# power.net
KiCad netlist of a schematic drawn in EAGLE
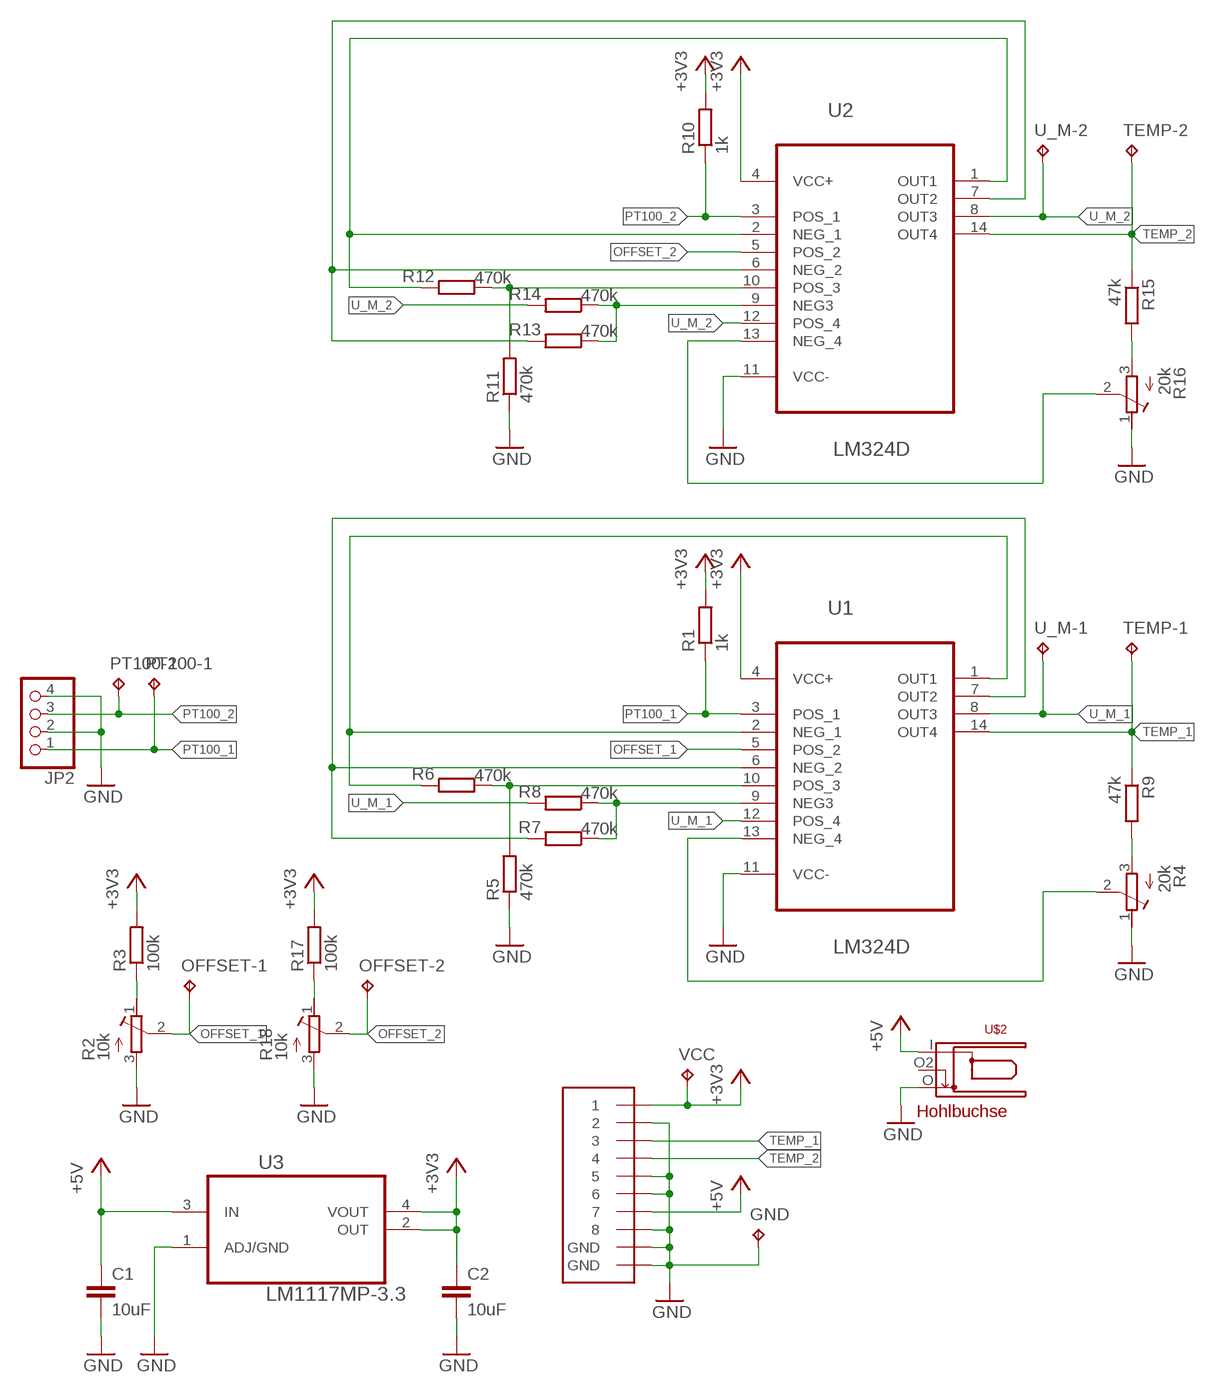
[diagram p0: schematic, sheet 1]

(export (version "E")
  (design (tool "Eeschema 10.0.6"))
  (components
    (comp (ref "C1")
      (value "10uF")
      (footprint "eagle-import:C0805")
      (libsource (lib "eagle-import") (part "C-EUC0805"))
    )
    (comp (ref "C2")
      (value "10uF")
      (footprint "eagle-import:C0805")
      (libsource (lib "eagle-import") (part "C-EUC0805"))
    )
    (comp (ref "GND")
      (value "TPB1,27")
      (footprint "eagle-import:B1,27")
      (libsource (lib "eagle-import") (part "TPB1,27"))
    )
    (comp (ref "JP2")
      (value "PINHD-1X4/90")
      (footprint "eagle-import:1X04_90")
      (libsource (lib "eagle-import") (part "PINHD-1X4/90"))
    )
    (comp (ref "OFFSET-1")
      (value "TPB1,27")
      (footprint "eagle-import:B1,27")
      (libsource (lib "eagle-import") (part "TPB1,27"))
    )
    (comp (ref "OFFSET-2")
      (value "TPB1,27")
      (footprint "eagle-import:B1,27")
      (libsource (lib "eagle-import") (part "TPB1,27"))
    )
    (comp (ref "PT100-1")
      (value "TPB1,27")
      (footprint "eagle-import:B1,27")
      (libsource (lib "eagle-import") (part "TPB1,27"))
    )
    (comp (ref "PT100-2")
      (value "TPB1,27")
      (footprint "eagle-import:B1,27")
      (libsource (lib "eagle-import") (part "TPB1,27"))
    )
    (comp (ref "R1")
      (value "1k")
      (footprint "eagle-import:R0805")
      (libsource (lib "eagle-import") (part "R-EU_R0805"))
    )
    (comp (ref "R2")
      (value "10k")
      (footprint "eagle-import:RTRIMT93YB")
      (libsource (lib "eagle-import") (part "R-TRIMMT93YB"))
    )
    (comp (ref "R3")
      (value "100k")
      (footprint "eagle-import:R0805")
      (libsource (lib "eagle-import") (part "R-EU_R0805"))
    )
    (comp (ref "R4")
      (value "20k")
      (footprint "eagle-import:RTRIMT93YB")
      (libsource (lib "eagle-import") (part "R-TRIMMT93YB"))
    )
    (comp (ref "R5")
      (value "470k")
      (footprint "eagle-import:R0805")
      (libsource (lib "eagle-import") (part "R-EU_R0805"))
    )
    (comp (ref "R6")
      (value "470k")
      (footprint "eagle-import:R0805")
      (libsource (lib "eagle-import") (part "R-EU_R0805"))
    )
    (comp (ref "R7")
      (value "470k")
      (footprint "eagle-import:R0805")
      (libsource (lib "eagle-import") (part "R-EU_R0805"))
    )
    (comp (ref "R8")
      (value "470k")
      (footprint "eagle-import:R0805")
      (libsource (lib "eagle-import") (part "R-EU_R0805"))
    )
    (comp (ref "R9")
      (value "47k")
      (footprint "eagle-import:R0805")
      (libsource (lib "eagle-import") (part "R-EU_R0805"))
    )
    (comp (ref "R10")
      (value "1k")
      (footprint "eagle-import:R0805")
      (libsource (lib "eagle-import") (part "R-EU_R0805"))
    )
    (comp (ref "R11")
      (value "470k")
      (footprint "eagle-import:R0805")
      (libsource (lib "eagle-import") (part "R-EU_R0805"))
    )
    (comp (ref "R12")
      (value "470k")
      (footprint "eagle-import:R0805")
      (libsource (lib "eagle-import") (part "R-EU_R0805"))
    )
    (comp (ref "R13")
      (value "470k")
      (footprint "eagle-import:R0805")
      (libsource (lib "eagle-import") (part "R-EU_R0805"))
    )
    (comp (ref "R14")
      (value "470k")
      (footprint "eagle-import:R0805")
      (libsource (lib "eagle-import") (part "R-EU_R0805"))
    )
    (comp (ref "R15")
      (value "47k")
      (footprint "eagle-import:R0805")
      (libsource (lib "eagle-import") (part "R-EU_R0805"))
    )
    (comp (ref "R16")
      (value "20k")
      (footprint "eagle-import:RTRIMT93YB")
      (libsource (lib "eagle-import") (part "R-TRIMMT93YB"))
    )
    (comp (ref "R17")
      (value "100k")
      (footprint "eagle-import:R0805")
      (libsource (lib "eagle-import") (part "R-EU_R0805"))
    )
    (comp (ref "R18")
      (value "10k")
      (footprint "eagle-import:RTRIMT93YB")
      (libsource (lib "eagle-import") (part "R-TRIMMT93YB"))
    )
    (comp (ref "TEMP-1")
      (value "TPB1,27")
      (footprint "eagle-import:B1,27")
      (libsource (lib "eagle-import") (part "TPB1,27"))
    )
    (comp (ref "TEMP-2")
      (value "TPB1,27")
      (footprint "eagle-import:B1,27")
      (libsource (lib "eagle-import") (part "TPB1,27"))
    )
    (comp (ref "U$1")
      (value "MEBP8-8G")
      (footprint "eagle-import:RJ45-REICHELT")
      (libsource (lib "eagle-import") (part "MEBP8-8G"))
    )
    (comp (ref "U$2")
      (value "HOHLBUCHSE")
      (footprint "eagle-import:HOHLBUCHSE")
      (libsource (lib "eagle-import") (part "HOHLBUCHSE"))
    )
    (comp (ref "U1")
      (value "LM324D")
      (footprint "eagle-import:SOIC127P600X175-14N")
      (libsource (lib "eagle-import") (part "LM324D"))
    )
    (comp (ref "U2")
      (value "LM324D")
      (footprint "eagle-import:SOIC127P600X175-14N")
      (libsource (lib "eagle-import") (part "LM324D"))
    )
    (comp (ref "U3")
      (value "LM1117MP-3.3")
      (footprint "eagle-import:SOT230P696X180-4N")
      (libsource (lib "eagle-import") (part "LM1117MP-3.3"))
    )
    (comp (ref "U_M-1")
      (value "TPB1,27")
      (footprint "eagle-import:B1,27")
      (libsource (lib "eagle-import") (part "TPB1,27"))
    )
    (comp (ref "U_M-2")
      (value "TPB1,27")
      (footprint "eagle-import:B1,27")
      (libsource (lib "eagle-import") (part "TPB1,27"))
    )
    (comp (ref "VCC")
      (value "TPB1,27")
      (footprint "eagle-import:B1,27")
      (libsource (lib "eagle-import") (part "TPB1,27"))
    )
  )
  (nets
    (net (code "1") (name "+3V3") (class "Default")
      (node (ref "C2") (pin "1") (pinfunction "1_1") (pintype "passive"))
      (node (ref "R1") (pin "2") (pinfunction "2_2") (pintype "passive"))
      (node (ref "R10") (pin "2") (pinfunction "2_2") (pintype "passive"))
      (node (ref "R17") (pin "2") (pinfunction "2_2") (pintype "passive"))
      (node (ref "R3") (pin "2") (pinfunction "2_2") (pintype "passive"))
      (node (ref "U$1") (pin "1") (pinfunction "1_1") (pintype "bidirectional"))
      (node (ref "U1") (pin "4") (pinfunction "VCC+_4") (pintype "power_in"))
      (node (ref "U2") (pin "4") (pinfunction "VCC+_4") (pintype "power_in"))
      (node (ref "U3") (pin "2") (pinfunction "OUT_2") (pintype "output"))
      (node (ref "U3") (pin "4") (pinfunction "VOUT_4") (pintype "output"))
      (node (ref "VCC") (pin "TP") (pinfunction "TP_TP") (pintype "input"))
    )
    (net (code "2") (name "+5V") (class "Default")
      (node (ref "C1") (pin "1") (pinfunction "1_1") (pintype "passive"))
      (node (ref "U$1") (pin "7") (pinfunction "7_7") (pintype "bidirectional"))
      (node (ref "U$2") (pin "I") (pinfunction "I_I") (pintype "bidirectional"))
      (node (ref "U3") (pin "3") (pinfunction "IN_3") (pintype "input"))
    )
    (net (code "3") (name "GND") (class "Default")
      (node (ref "C1") (pin "2") (pinfunction "2_2") (pintype "passive"))
      (node (ref "C2") (pin "2") (pinfunction "2_2") (pintype "passive"))
      (node (ref "GND") (pin "TP") (pinfunction "TP_TP") (pintype "input"))
      (node (ref "JP2") (pin "2") (pinfunction "2_2") (pintype "passive"))
      (node (ref "JP2") (pin "4") (pinfunction "4_4") (pintype "passive"))
      (node (ref "R11") (pin "1") (pinfunction "1_1") (pintype "passive"))
      (node (ref "R16") (pin "1") (pinfunction "E_1") (pintype "passive"))
      (node (ref "R18") (pin "3") (pinfunction "A_3") (pintype "passive"))
      (node (ref "R2") (pin "3") (pinfunction "A_3") (pintype "passive"))
      (node (ref "R4") (pin "1") (pinfunction "E_1") (pintype "passive"))
      (node (ref "R5") (pin "1") (pinfunction "1_1") (pintype "passive"))
      (node (ref "U$1") (pin "2") (pinfunction "2_2") (pintype "bidirectional"))
      (node (ref "U$1") (pin "5") (pinfunction "5_5") (pintype "bidirectional"))
      (node (ref "U$1") (pin "6") (pinfunction "6_6") (pintype "bidirectional"))
      (node (ref "U$1") (pin "8") (pinfunction "8_8") (pintype "bidirectional"))
      (node (ref "U$1") (pin "GND@1") (pinfunction "GND_GND@1") (pintype "power_in"))
      (node (ref "U$1") (pin "GND@2") (pinfunction "GND_GND@2") (pintype "power_in"))
      (node (ref "U$2") (pin "O") (pinfunction "O_O") (pintype "bidirectional"))
      (node (ref "U1") (pin "11") (pinfunction "VCC-_11") (pintype "power_in"))
      (node (ref "U2") (pin "11") (pinfunction "VCC-_11") (pintype "power_in"))
      (node (ref "U3") (pin "1") (pinfunction "ADJ/GND_1") (pintype "passive"))
    )
    (net (code "4") (name "Net-(R2-E)") (class "Default")
      (node (ref "R2") (pin "1") (pinfunction "E_1") (pintype "passive"))
      (node (ref "R3") (pin "1") (pinfunction "1_1") (pintype "passive"))
    )
    (net (code "5") (name "Net-(R4-A)") (class "Default")
      (node (ref "R4") (pin "3") (pinfunction "A_3") (pintype "passive"))
      (node (ref "R9") (pin "2") (pinfunction "2_2") (pintype "passive"))
    )
    (net (code "6") (name "Net-(R4-S)") (class "Default")
      (node (ref "R4") (pin "2") (pinfunction "S_2") (pintype "passive"))
      (node (ref "U1") (pin "13") (pinfunction "NEG_4_13") (pintype "input"))
    )
    (net (code "7") (name "Net-(R16-A)") (class "Default")
      (node (ref "R15") (pin "2") (pinfunction "2_2") (pintype "passive"))
      (node (ref "R16") (pin "3") (pinfunction "A_3") (pintype "passive"))
    )
    (net (code "8") (name "Net-(R16-S)") (class "Default")
      (node (ref "R16") (pin "2") (pinfunction "S_2") (pintype "passive"))
      (node (ref "U2") (pin "13") (pinfunction "NEG_4_13") (pintype "input"))
    )
    (net (code "9") (name "Net-(R18-E)") (class "Default")
      (node (ref "R17") (pin "1") (pinfunction "1_1") (pintype "passive"))
      (node (ref "R18") (pin "1") (pinfunction "E_1") (pintype "passive"))
    )
    (net (code "10") (name "Net-(U1-NEG3)") (class "Default")
      (node (ref "R7") (pin "1") (pinfunction "1_1") (pintype "passive"))
      (node (ref "R8") (pin "1") (pinfunction "1_1") (pintype "passive"))
      (node (ref "U1") (pin "9") (pinfunction "NEG3_9") (pintype "input"))
    )
    (net (code "11") (name "Net-(U1-NEG_1)") (class "Default")
      (node (ref "R6") (pin "2") (pinfunction "2_2") (pintype "passive"))
      (node (ref "U1") (pin "1") (pinfunction "OUT1_1") (pintype "output"))
      (node (ref "U1") (pin "2") (pinfunction "NEG_1_2") (pintype "input"))
    )
    (net (code "12") (name "Net-(U1-NEG_2)") (class "Default")
      (node (ref "R7") (pin "2") (pinfunction "2_2") (pintype "passive"))
      (node (ref "U1") (pin "6") (pinfunction "NEG_2_6") (pintype "input"))
      (node (ref "U1") (pin "7") (pinfunction "OUT2_7") (pintype "output"))
    )
    (net (code "13") (name "Net-(U1-POS_3)") (class "Default")
      (node (ref "R5") (pin "2") (pinfunction "2_2") (pintype "passive"))
      (node (ref "R6") (pin "1") (pinfunction "1_1") (pintype "passive"))
      (node (ref "U1") (pin "10") (pinfunction "POS_3_10") (pintype "input"))
    )
    (net (code "14") (name "Net-(U2-NEG3)") (class "Default")
      (node (ref "R13") (pin "1") (pinfunction "1_1") (pintype "passive"))
      (node (ref "R14") (pin "1") (pinfunction "1_1") (pintype "passive"))
      (node (ref "U2") (pin "9") (pinfunction "NEG3_9") (pintype "input"))
    )
    (net (code "15") (name "Net-(U2-NEG_1)") (class "Default")
      (node (ref "R12") (pin "2") (pinfunction "2_2") (pintype "passive"))
      (node (ref "U2") (pin "1") (pinfunction "OUT1_1") (pintype "output"))
      (node (ref "U2") (pin "2") (pinfunction "NEG_1_2") (pintype "input"))
    )
    (net (code "16") (name "Net-(U2-NEG_2)") (class "Default")
      (node (ref "R13") (pin "2") (pinfunction "2_2") (pintype "passive"))
      (node (ref "U2") (pin "6") (pinfunction "NEG_2_6") (pintype "input"))
      (node (ref "U2") (pin "7") (pinfunction "OUT2_7") (pintype "output"))
    )
    (net (code "17") (name "Net-(U2-POS_3)") (class "Default")
      (node (ref "R11") (pin "2") (pinfunction "2_2") (pintype "passive"))
      (node (ref "R12") (pin "1") (pinfunction "1_1") (pintype "passive"))
      (node (ref "U2") (pin "10") (pinfunction "POS_3_10") (pintype "input"))
    )
    (net (code "18") (name "OFFSET_1") (class "Default")
      (node (ref "OFFSET-1") (pin "TP") (pinfunction "TP_TP") (pintype "input"))
      (node (ref "R2") (pin "2") (pinfunction "S_2") (pintype "passive"))
      (node (ref "U1") (pin "5") (pinfunction "POS_2_5") (pintype "input"))
    )
    (net (code "19") (name "OFFSET_2") (class "Default")
      (node (ref "OFFSET-2") (pin "TP") (pinfunction "TP_TP") (pintype "input"))
      (node (ref "R18") (pin "2") (pinfunction "S_2") (pintype "passive"))
      (node (ref "U2") (pin "5") (pinfunction "POS_2_5") (pintype "input"))
    )
    (net (code "20") (name "PT100_1") (class "Default")
      (node (ref "JP2") (pin "1") (pinfunction "1_1") (pintype "passive"))
      (node (ref "PT100-1") (pin "TP") (pinfunction "TP_TP") (pintype "input"))
      (node (ref "R1") (pin "1") (pinfunction "1_1") (pintype "passive"))
      (node (ref "U1") (pin "3") (pinfunction "POS_1_3") (pintype "input"))
    )
    (net (code "21") (name "PT100_2") (class "Default")
      (node (ref "JP2") (pin "3") (pinfunction "3_3") (pintype "passive"))
      (node (ref "PT100-2") (pin "TP") (pinfunction "TP_TP") (pintype "input"))
      (node (ref "R10") (pin "1") (pinfunction "1_1") (pintype "passive"))
      (node (ref "U2") (pin "3") (pinfunction "POS_1_3") (pintype "input"))
    )
    (net (code "22") (name "TEMP_1") (class "Default")
      (node (ref "R9") (pin "1") (pinfunction "1_1") (pintype "passive"))
      (node (ref "TEMP-1") (pin "TP") (pinfunction "TP_TP") (pintype "input"))
      (node (ref "U$1") (pin "3") (pinfunction "3_3") (pintype "bidirectional"))
      (node (ref "U1") (pin "14") (pinfunction "OUT4_14") (pintype "output"))
    )
    (net (code "23") (name "TEMP_2") (class "Default")
      (node (ref "R15") (pin "1") (pinfunction "1_1") (pintype "passive"))
      (node (ref "TEMP-2") (pin "TP") (pinfunction "TP_TP") (pintype "input"))
      (node (ref "U$1") (pin "4") (pinfunction "4_4") (pintype "bidirectional"))
      (node (ref "U2") (pin "14") (pinfunction "OUT4_14") (pintype "output"))
    )
    (net (code "24") (name "U_M_1") (class "Default")
      (node (ref "R8") (pin "2") (pinfunction "2_2") (pintype "passive"))
      (node (ref "U1") (pin "12") (pinfunction "POS_4_12") (pintype "input"))
      (node (ref "U1") (pin "8") (pinfunction "OUT3_8") (pintype "output"))
      (node (ref "U_M-1") (pin "TP") (pinfunction "TP_TP") (pintype "input"))
    )
    (net (code "25") (name "U_M_2") (class "Default")
      (node (ref "R14") (pin "2") (pinfunction "2_2") (pintype "passive"))
      (node (ref "U2") (pin "12") (pinfunction "POS_4_12") (pintype "input"))
      (node (ref "U2") (pin "8") (pinfunction "OUT3_8") (pintype "output"))
      (node (ref "U_M-2") (pin "TP") (pinfunction "TP_TP") (pintype "input"))
    )
    (net (code "26") (name "unconnected-(U$2-PadO2)") (class "Default")
      (node (ref "U$2") (pin "O2") (pinfunction "O2_O2") (pintype "bidirectional"))
    )
  )
)
